# Stepperdriver.net
KiCad netlist of a schematic drawn in EAGLE
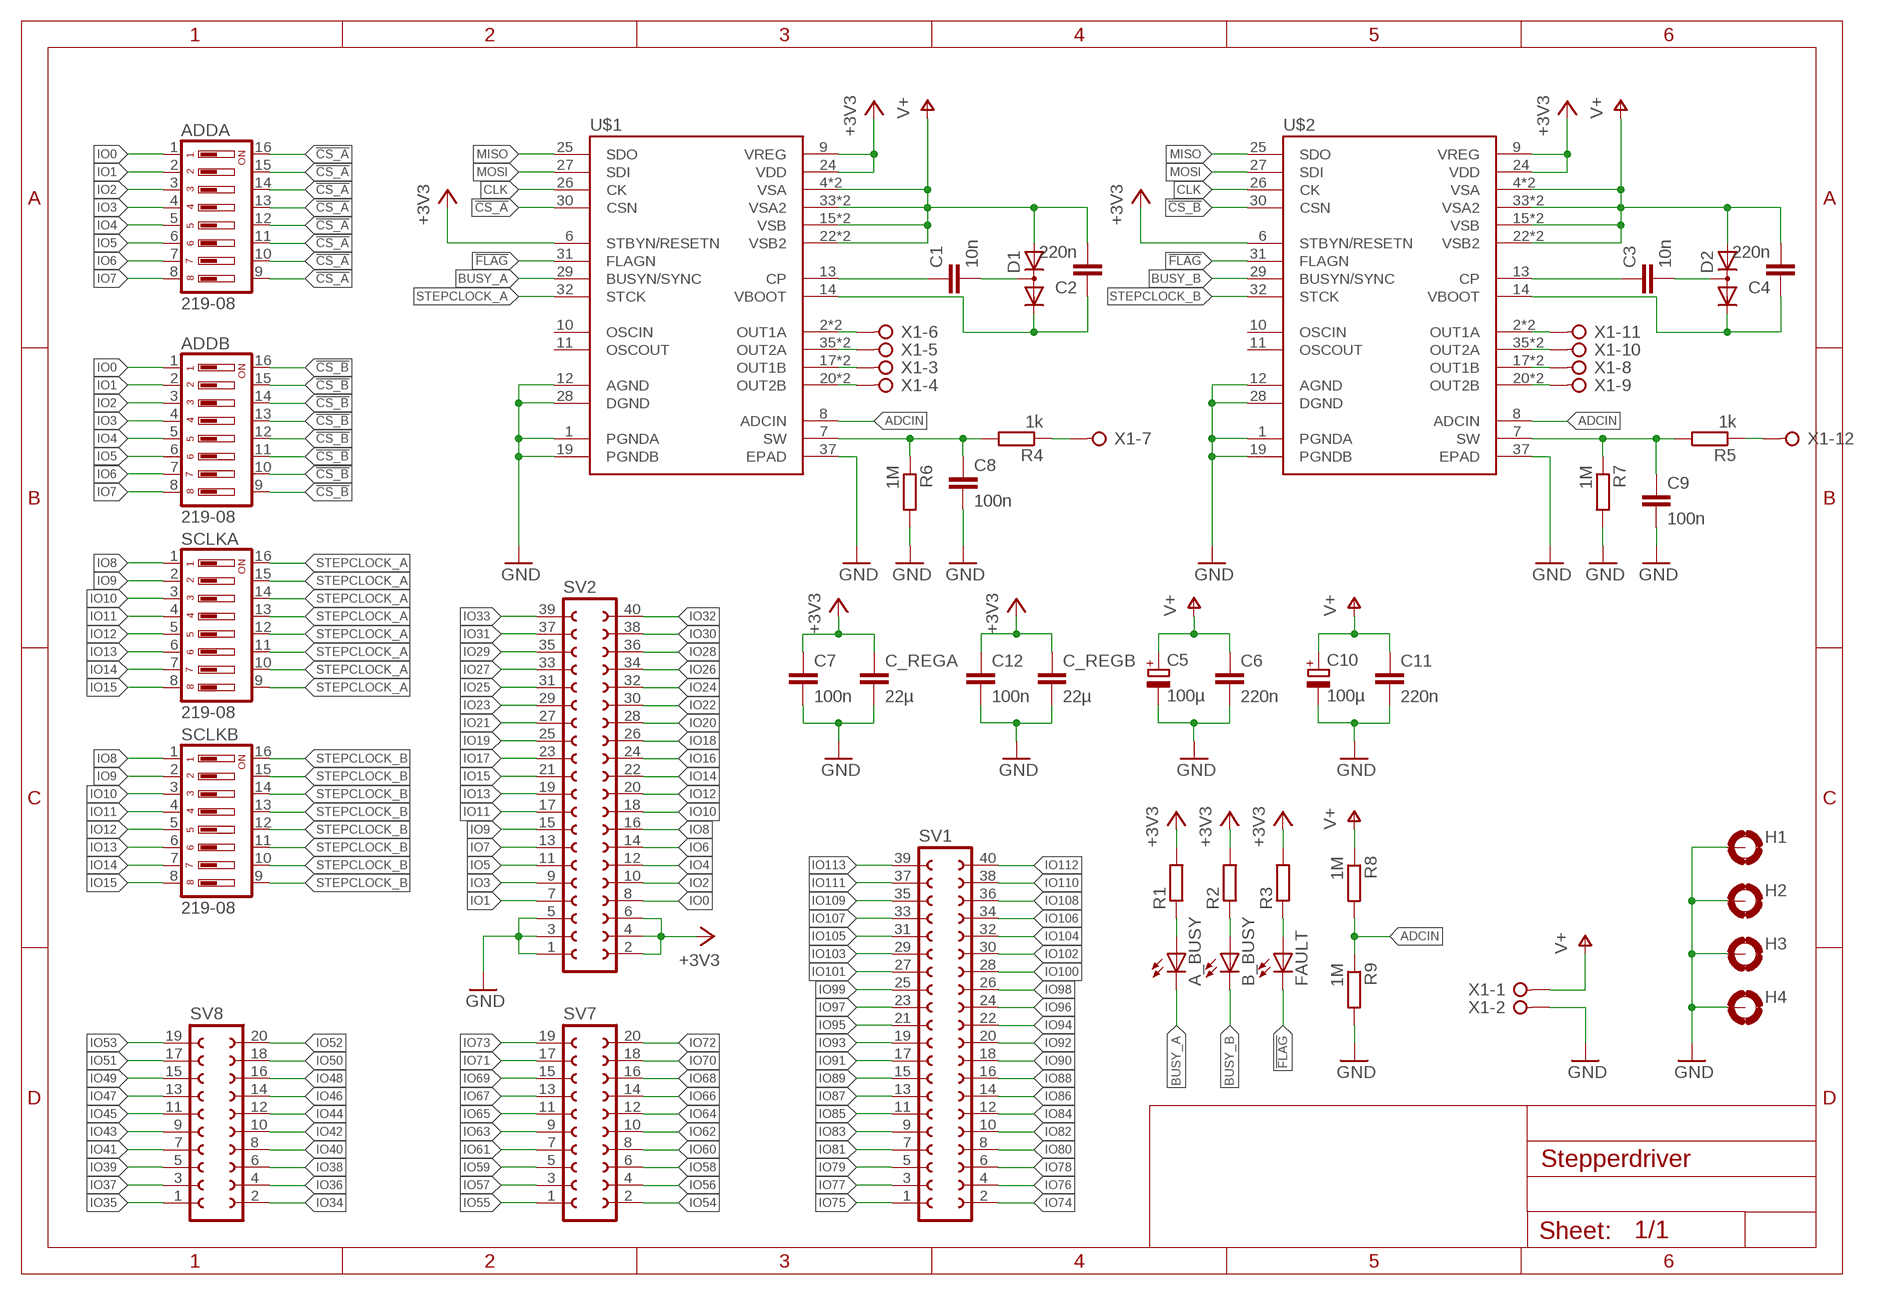
[diagram p0: schematic, sheet 1]

(export (version "E")
  (design (tool "Eeschema 10.0.6"))
  (components
    (comp (ref "ADDA")
      (value "219-08")
      (footprint "eagle-import:CTS-219-08")
      (libsource (lib "eagle-import") (part "219-08"))
    )
    (comp (ref "ADDB")
      (value "219-08")
      (footprint "eagle-import:CTS-219-08")
      (libsource (lib "eagle-import") (part "219-08"))
    )
    (comp (ref "A_BUSY")
      (value "LEDCHIP-LED0805")
      (footprint "eagle-import:CHIP-LED0805")
      (libsource (lib "eagle-import") (part "LEDCHIP-LED0805"))
    )
    (comp (ref "B_BUSY")
      (value "LEDCHIP-LED0805")
      (footprint "eagle-import:CHIP-LED0805")
      (libsource (lib "eagle-import") (part "LEDCHIP-LED0805"))
    )
    (comp (ref "C1")
      (value "10n")
      (footprint "eagle-import:C0805")
      (libsource (lib "eagle-import") (part "C-EUC0805"))
    )
    (comp (ref "C2")
      (value "220n")
      (footprint "eagle-import:C0805")
      (libsource (lib "eagle-import") (part "C-EUC0805"))
    )
    (comp (ref "C3")
      (value "10n")
      (footprint "eagle-import:C0805")
      (libsource (lib "eagle-import") (part "C-EUC0805"))
    )
    (comp (ref "C4")
      (value "220n")
      (footprint "eagle-import:C0805")
      (libsource (lib "eagle-import") (part "C-EUC0805"))
    )
    (comp (ref "C5")
      (value "100µ")
      (footprint "eagle-import:150CLZ-1010")
      (libsource (lib "eagle-import") (part "CPOL-EU150CLZ-1010"))
    )
    (comp (ref "C6")
      (value "220n")
      (footprint "eagle-import:C0805")
      (libsource (lib "eagle-import") (part "C-EUC0805"))
    )
    (comp (ref "C7")
      (value "100n")
      (footprint "eagle-import:C0805")
      (libsource (lib "eagle-import") (part "C-EUC0805"))
    )
    (comp (ref "C8")
      (value "100n")
      (footprint "eagle-import:C0805")
      (libsource (lib "eagle-import") (part "C-EUC0805"))
    )
    (comp (ref "C9")
      (value "100n")
      (footprint "eagle-import:C0805")
      (libsource (lib "eagle-import") (part "C-EUC0805"))
    )
    (comp (ref "C10")
      (value "100µ")
      (footprint "eagle-import:150CLZ-1010")
      (libsource (lib "eagle-import") (part "CPOL-EU150CLZ-1010"))
    )
    (comp (ref "C11")
      (value "220n")
      (footprint "eagle-import:C0805")
      (libsource (lib "eagle-import") (part "C-EUC0805"))
    )
    (comp (ref "C12")
      (value "100n")
      (footprint "eagle-import:C0805")
      (libsource (lib "eagle-import") (part "C-EUC0805"))
    )
    (comp (ref "C_REGA")
      (value "22µ")
      (footprint "eagle-import:C0805")
      (libsource (lib "eagle-import") (part "C-EUC0805"))
    )
    (comp (ref "C_REGB")
      (value "22µ")
      (footprint "eagle-import:C0805")
      (libsource (lib "eagle-import") (part "C-EUC0805"))
    )
    (comp (ref "D1")
      (value "DIODE_2CACA-SOT23")
      (footprint "eagle-import:SOT23")
      (libsource (lib "eagle-import") (part "DIODE_2CACA-SOT23"))
    )
    (comp (ref "D2")
      (value "DIODE_2CACA-SOT23")
      (footprint "eagle-import:SOT23")
      (libsource (lib "eagle-import") (part "DIODE_2CACA-SOT23"))
    )
    (comp (ref "FAULT")
      (value "LEDCHIP-LED0805")
      (footprint "eagle-import:CHIP-LED0805")
      (libsource (lib "eagle-import") (part "LEDCHIP-LED0805"))
    )
    (comp (ref "H1")
      (value "MOUNT-PAD-ROUND5.0")
      (footprint "eagle-import:5,0-PAD")
      (libsource (lib "eagle-import") (part "MOUNT-PAD-ROUND5.0"))
    )
    (comp (ref "H2")
      (value "MOUNT-PAD-ROUND5.0")
      (footprint "eagle-import:5,0-PAD")
      (libsource (lib "eagle-import") (part "MOUNT-PAD-ROUND5.0"))
    )
    (comp (ref "H3")
      (value "MOUNT-PAD-ROUND5.0")
      (footprint "eagle-import:5,0-PAD")
      (libsource (lib "eagle-import") (part "MOUNT-PAD-ROUND5.0"))
    )
    (comp (ref "H4")
      (value "MOUNT-PAD-ROUND5.0")
      (footprint "eagle-import:5,0-PAD")
      (libsource (lib "eagle-import") (part "MOUNT-PAD-ROUND5.0"))
    )
    (comp (ref "R1")
      (value "R-EU_R0805")
      (footprint "eagle-import:R0805")
      (libsource (lib "eagle-import") (part "R-EU_R0805"))
    )
    (comp (ref "R2")
      (value "R-EU_R0805")
      (footprint "eagle-import:R0805")
      (libsource (lib "eagle-import") (part "R-EU_R0805"))
    )
    (comp (ref "R3")
      (value "R-EU_R0805")
      (footprint "eagle-import:R0805")
      (libsource (lib "eagle-import") (part "R-EU_R0805"))
    )
    (comp (ref "R4")
      (value "1k")
      (footprint "eagle-import:R0805")
      (libsource (lib "eagle-import") (part "R-EU_R0805"))
    )
    (comp (ref "R5")
      (value "1k")
      (footprint "eagle-import:R0805")
      (libsource (lib "eagle-import") (part "R-EU_R0805"))
    )
    (comp (ref "R6")
      (value "1M")
      (footprint "eagle-import:R0805")
      (libsource (lib "eagle-import") (part "R-EU_R0805"))
    )
    (comp (ref "R7")
      (value "1M")
      (footprint "eagle-import:R0805")
      (libsource (lib "eagle-import") (part "R-EU_R0805"))
    )
    (comp (ref "R8")
      (value "1M")
      (footprint "eagle-import:R0805")
      (libsource (lib "eagle-import") (part "R-EU_R0805"))
    )
    (comp (ref "R9")
      (value "1M")
      (footprint "eagle-import:R0805")
      (libsource (lib "eagle-import") (part "R-EU_R0805"))
    )
    (comp (ref "SCLKA")
      (value "219-08")
      (footprint "eagle-import:CTS-219-08")
      (libsource (lib "eagle-import") (part "219-08"))
    )
    (comp (ref "SCLKB")
      (value "219-08")
      (footprint "eagle-import:CTS-219-08")
      (libsource (lib "eagle-import") (part "219-08"))
    )
    (comp (ref "SV1")
      (value "FE20-2")
      (footprint "eagle-import:FE20-2")
      (libsource (lib "eagle-import") (part "FE20-2"))
    )
    (comp (ref "SV2")
      (value "FE20-2")
      (footprint "eagle-import:FE20-2")
      (libsource (lib "eagle-import") (part "FE20-2"))
    )
    (comp (ref "SV7")
      (value "FE10-2")
      (footprint "eagle-import:FE10-2")
      (fields (field (name "OC_FARNELL") "unknown") (field (name "OC_NEWARK") "unknown"))
      (libsource (lib "eagle-import") (part "FE10-2"))
    )
    (comp (ref "SV8")
      (value "FE10-2")
      (footprint "eagle-import:FE10-2")
      (fields (field (name "OC_FARNELL") "unknown") (field (name "OC_NEWARK") "unknown"))
      (libsource (lib "eagle-import") (part "FE10-2"))
    )
    (comp (ref "U$1")
      (value "L6470HPOWERSO36")
      (footprint "eagle-import:SOP65P1400X360-37N")
      (libsource (lib "eagle-import") (part "L6470HPOWERSO36"))
    )
    (comp (ref "U$2")
      (value "L6470HPOWERSO36")
      (footprint "eagle-import:SOP65P1400X360-37N")
      (libsource (lib "eagle-import") (part "L6470HPOWERSO36"))
    )
    (comp (ref "X1")
      (value "W237-12P")
      (footprint "eagle-import:W237-12P")
      (libsource (lib "eagle-import") (part "W237-12P"))
    )
  )
  (nets
    (net (code "1") (name "+3V3") (class "Default")
      (node (ref "C12") (pin "1") (pinfunction "1_1") (pintype "passive"))
      (node (ref "C7") (pin "1") (pinfunction "1_1") (pintype "passive"))
      (node (ref "C_REGA") (pin "1") (pinfunction "1_1") (pintype "passive"))
      (node (ref "C_REGB") (pin "1") (pinfunction "1_1") (pintype "passive"))
      (node (ref "R1") (pin "2") (pinfunction "2_2") (pintype "passive"))
      (node (ref "R2") (pin "2") (pinfunction "2_2") (pintype "passive"))
      (node (ref "R3") (pin "2") (pinfunction "2_2") (pintype "passive"))
      (node (ref "SV2") (pin "2") (pinfunction "2_2") (pintype "passive"))
      (node (ref "SV2") (pin "4") (pinfunction "4_4") (pintype "passive"))
      (node (ref "SV2") (pin "6") (pinfunction "6_6") (pintype "passive"))
      (node (ref "U$1") (pin "24") (pinfunction "VDD_24") (pintype "bidirectional"))
      (node (ref "U$1") (pin "6") (pinfunction "STBYN/RESETN_6") (pintype "bidirectional"))
      (node (ref "U$1") (pin "9") (pinfunction "VREG_9") (pintype "bidirectional"))
      (node (ref "U$2") (pin "24") (pinfunction "VDD_24") (pintype "bidirectional"))
      (node (ref "U$2") (pin "6") (pinfunction "STBYN/RESETN_6") (pintype "bidirectional"))
      (node (ref "U$2") (pin "9") (pinfunction "VREG_9") (pintype "bidirectional"))
    )
    (net (code "2") (name "/~{CS_A}") (class "Default")
      (node (ref "ADDA") (pin "10") (pinfunction "10_10") (pintype "passive"))
      (node (ref "ADDA") (pin "11") (pinfunction "11_11") (pintype "passive"))
      (node (ref "ADDA") (pin "12") (pinfunction "12_12") (pintype "passive"))
      (node (ref "ADDA") (pin "13") (pinfunction "13_13") (pintype "passive"))
      (node (ref "ADDA") (pin "14") (pinfunction "14_14") (pintype "passive"))
      (node (ref "ADDA") (pin "15") (pinfunction "15_15") (pintype "passive"))
      (node (ref "ADDA") (pin "16") (pinfunction "16_16") (pintype "passive"))
      (node (ref "ADDA") (pin "9") (pinfunction "9_9") (pintype "passive"))
      (node (ref "U$1") (pin "30") (pinfunction "CSN_30") (pintype "bidirectional"))
    )
    (net (code "3") (name "/~{CS_B}") (class "Default")
      (node (ref "ADDB") (pin "10") (pinfunction "10_10") (pintype "passive"))
      (node (ref "ADDB") (pin "11") (pinfunction "11_11") (pintype "passive"))
      (node (ref "ADDB") (pin "12") (pinfunction "12_12") (pintype "passive"))
      (node (ref "ADDB") (pin "13") (pinfunction "13_13") (pintype "passive"))
      (node (ref "ADDB") (pin "14") (pinfunction "14_14") (pintype "passive"))
      (node (ref "ADDB") (pin "15") (pinfunction "15_15") (pintype "passive"))
      (node (ref "ADDB") (pin "16") (pinfunction "16_16") (pintype "passive"))
      (node (ref "ADDB") (pin "9") (pinfunction "9_9") (pintype "passive"))
      (node (ref "U$2") (pin "30") (pinfunction "CSN_30") (pintype "bidirectional"))
    )
    (net (code "4") (name "/~{FLAG}") (class "Default")
      (node (ref "FAULT") (pin "C") (pinfunction "C_C") (pintype "passive"))
      (node (ref "U$1") (pin "31") (pinfunction "FLAGN_31") (pintype "bidirectional"))
      (node (ref "U$2") (pin "31") (pinfunction "FLAGN_31") (pintype "bidirectional"))
    )
    (net (code "5") (name "ADCIN") (class "Default")
      (node (ref "R8") (pin "2") (pinfunction "2_2") (pintype "passive"))
      (node (ref "R9") (pin "1") (pinfunction "1_1") (pintype "passive"))
      (node (ref "U$1") (pin "8") (pinfunction "ADCIN_8") (pintype "bidirectional"))
      (node (ref "U$2") (pin "8") (pinfunction "ADCIN_8") (pintype "bidirectional"))
    )
    (net (code "6") (name "BUSY_A") (class "Default")
      (node (ref "A_BUSY") (pin "C") (pinfunction "C_C") (pintype "passive"))
      (node (ref "U$1") (pin "29") (pinfunction "BUSYN/SYNC_29") (pintype "bidirectional"))
    )
    (net (code "7") (name "BUSY_B") (class "Default")
      (node (ref "B_BUSY") (pin "C") (pinfunction "C_C") (pintype "passive"))
      (node (ref "U$2") (pin "29") (pinfunction "BUSYN/SYNC_29") (pintype "bidirectional"))
    )
    (net (code "8") (name "CLK") (class "Default")
      (node (ref "U$1") (pin "26") (pinfunction "CK_26") (pintype "bidirectional"))
      (node (ref "U$2") (pin "26") (pinfunction "CK_26") (pintype "bidirectional"))
    )
    (net (code "9") (name "GND") (class "Default")
      (node (ref "C10") (pin "-") (pinfunction "-_-") (pintype "passive"))
      (node (ref "C11") (pin "2") (pinfunction "2_2") (pintype "passive"))
      (node (ref "C12") (pin "2") (pinfunction "2_2") (pintype "passive"))
      (node (ref "C5") (pin "-") (pinfunction "-_-") (pintype "passive"))
      (node (ref "C6") (pin "2") (pinfunction "2_2") (pintype "passive"))
      (node (ref "C7") (pin "2") (pinfunction "2_2") (pintype "passive"))
      (node (ref "C8") (pin "2") (pinfunction "2_2") (pintype "passive"))
      (node (ref "C9") (pin "2") (pinfunction "2_2") (pintype "passive"))
      (node (ref "C_REGA") (pin "2") (pinfunction "2_2") (pintype "passive"))
      (node (ref "C_REGB") (pin "2") (pinfunction "2_2") (pintype "passive"))
      (node (ref "H1") (pin "B5") (pinfunction "MOUNT_B5") (pintype "passive"))
      (node (ref "H2") (pin "B5") (pinfunction "MOUNT_B5") (pintype "passive"))
      (node (ref "H3") (pin "B5") (pinfunction "MOUNT_B5") (pintype "passive"))
      (node (ref "H4") (pin "B5") (pinfunction "MOUNT_B5") (pintype "passive"))
      (node (ref "R6") (pin "2") (pinfunction "2_2") (pintype "passive"))
      (node (ref "R7") (pin "2") (pinfunction "2_2") (pintype "passive"))
      (node (ref "R9") (pin "2") (pinfunction "2_2") (pintype "passive"))
      (node (ref "SV2") (pin "1") (pinfunction "1_1") (pintype "passive"))
      (node (ref "SV2") (pin "3") (pinfunction "3_3") (pintype "passive"))
      (node (ref "SV2") (pin "5") (pinfunction "5_5") (pintype "passive"))
      (node (ref "U$1") (pin "1") (pinfunction "PGNDA_1") (pintype "bidirectional"))
      (node (ref "U$1") (pin "12") (pinfunction "AGND_12") (pintype "bidirectional"))
      (node (ref "U$1") (pin "19") (pinfunction "PGNDB_19") (pintype "bidirectional"))
      (node (ref "U$1") (pin "28") (pinfunction "DGND_28") (pintype "bidirectional"))
      (node (ref "U$1") (pin "37") (pinfunction "EPAD_37") (pintype "bidirectional"))
      (node (ref "U$2") (pin "1") (pinfunction "PGNDA_1") (pintype "bidirectional"))
      (node (ref "U$2") (pin "12") (pinfunction "AGND_12") (pintype "bidirectional"))
      (node (ref "U$2") (pin "19") (pinfunction "PGNDB_19") (pintype "bidirectional"))
      (node (ref "U$2") (pin "28") (pinfunction "DGND_28") (pintype "bidirectional"))
      (node (ref "U$2") (pin "37") (pinfunction "EPAD_37") (pintype "bidirectional"))
      (node (ref "X1") (pin "2") (pinfunction "KL_2") (pintype "passive"))
    )
    (net (code "10") (name "IO0") (class "Default")
      (node (ref "ADDA") (pin "1") (pinfunction "1_1") (pintype "passive"))
      (node (ref "ADDB") (pin "1") (pinfunction "1_1") (pintype "passive"))
      (node (ref "SV2") (pin "8") (pinfunction "8_8") (pintype "passive"))
    )
    (net (code "11") (name "IO1") (class "Default")
      (node (ref "ADDA") (pin "2") (pinfunction "2_2") (pintype "passive"))
      (node (ref "ADDB") (pin "2") (pinfunction "2_2") (pintype "passive"))
      (node (ref "SV2") (pin "7") (pinfunction "7_7") (pintype "passive"))
    )
    (net (code "12") (name "IO2") (class "Default")
      (node (ref "ADDA") (pin "3") (pinfunction "3_3") (pintype "passive"))
      (node (ref "ADDB") (pin "3") (pinfunction "3_3") (pintype "passive"))
      (node (ref "SV2") (pin "10") (pinfunction "10_10") (pintype "passive"))
    )
    (net (code "13") (name "IO3") (class "Default")
      (node (ref "ADDA") (pin "4") (pinfunction "4_4") (pintype "passive"))
      (node (ref "ADDB") (pin "4") (pinfunction "4_4") (pintype "passive"))
      (node (ref "SV2") (pin "9") (pinfunction "9_9") (pintype "passive"))
    )
    (net (code "14") (name "IO4") (class "Default")
      (node (ref "ADDA") (pin "5") (pinfunction "5_5") (pintype "passive"))
      (node (ref "ADDB") (pin "5") (pinfunction "5_5") (pintype "passive"))
      (node (ref "SV2") (pin "12") (pinfunction "12_12") (pintype "passive"))
    )
    (net (code "15") (name "IO5") (class "Default")
      (node (ref "ADDA") (pin "6") (pinfunction "6_6") (pintype "passive"))
      (node (ref "ADDB") (pin "6") (pinfunction "6_6") (pintype "passive"))
      (node (ref "SV2") (pin "11") (pinfunction "11_11") (pintype "passive"))
    )
    (net (code "16") (name "IO6") (class "Default")
      (node (ref "ADDA") (pin "7") (pinfunction "7_7") (pintype "passive"))
      (node (ref "ADDB") (pin "7") (pinfunction "7_7") (pintype "passive"))
      (node (ref "SV2") (pin "14") (pinfunction "14_14") (pintype "passive"))
    )
    (net (code "17") (name "IO7") (class "Default")
      (node (ref "ADDA") (pin "8") (pinfunction "8_8") (pintype "passive"))
      (node (ref "ADDB") (pin "8") (pinfunction "8_8") (pintype "passive"))
      (node (ref "SV2") (pin "13") (pinfunction "13_13") (pintype "passive"))
    )
    (net (code "18") (name "IO8") (class "Default")
      (node (ref "SCLKA") (pin "1") (pinfunction "1_1") (pintype "passive"))
      (node (ref "SCLKB") (pin "1") (pinfunction "1_1") (pintype "passive"))
      (node (ref "SV2") (pin "16") (pinfunction "16_16") (pintype "passive"))
    )
    (net (code "19") (name "IO9") (class "Default")
      (node (ref "SCLKA") (pin "2") (pinfunction "2_2") (pintype "passive"))
      (node (ref "SCLKB") (pin "2") (pinfunction "2_2") (pintype "passive"))
      (node (ref "SV2") (pin "15") (pinfunction "15_15") (pintype "passive"))
    )
    (net (code "20") (name "IO10") (class "Default")
      (node (ref "SCLKA") (pin "3") (pinfunction "3_3") (pintype "passive"))
      (node (ref "SCLKB") (pin "3") (pinfunction "3_3") (pintype "passive"))
      (node (ref "SV2") (pin "18") (pinfunction "18_18") (pintype "passive"))
    )
    (net (code "21") (name "IO11") (class "Default")
      (node (ref "SCLKA") (pin "4") (pinfunction "4_4") (pintype "passive"))
      (node (ref "SCLKB") (pin "4") (pinfunction "4_4") (pintype "passive"))
      (node (ref "SV2") (pin "17") (pinfunction "17_17") (pintype "passive"))
    )
    (net (code "22") (name "IO12") (class "Default")
      (node (ref "SCLKA") (pin "5") (pinfunction "5_5") (pintype "passive"))
      (node (ref "SCLKB") (pin "5") (pinfunction "5_5") (pintype "passive"))
      (node (ref "SV2") (pin "20") (pinfunction "20_20") (pintype "passive"))
    )
    (net (code "23") (name "IO13") (class "Default")
      (node (ref "SCLKA") (pin "6") (pinfunction "6_6") (pintype "passive"))
      (node (ref "SCLKB") (pin "6") (pinfunction "6_6") (pintype "passive"))
      (node (ref "SV2") (pin "19") (pinfunction "19_19") (pintype "passive"))
    )
    (net (code "24") (name "IO14") (class "Default")
      (node (ref "SCLKA") (pin "7") (pinfunction "7_7") (pintype "passive"))
      (node (ref "SCLKB") (pin "7") (pinfunction "7_7") (pintype "passive"))
      (node (ref "SV2") (pin "22") (pinfunction "22_22") (pintype "passive"))
    )
    (net (code "25") (name "IO15") (class "Default")
      (node (ref "SCLKA") (pin "8") (pinfunction "8_8") (pintype "passive"))
      (node (ref "SCLKB") (pin "8") (pinfunction "8_8") (pintype "passive"))
      (node (ref "SV2") (pin "21") (pinfunction "21_21") (pintype "passive"))
    )
    (net (code "26") (name "IO16") (class "Default")
      (node (ref "SV2") (pin "24") (pinfunction "24_24") (pintype "passive"))
    )
    (net (code "27") (name "IO17") (class "Default")
      (node (ref "SV2") (pin "23") (pinfunction "23_23") (pintype "passive"))
    )
    (net (code "28") (name "IO18") (class "Default")
      (node (ref "SV2") (pin "26") (pinfunction "26_26") (pintype "passive"))
    )
    (net (code "29") (name "IO19") (class "Default")
      (node (ref "SV2") (pin "25") (pinfunction "25_25") (pintype "passive"))
    )
    (net (code "30") (name "IO20") (class "Default")
      (node (ref "SV2") (pin "28") (pinfunction "28_28") (pintype "passive"))
    )
    (net (code "31") (name "IO21") (class "Default")
      (node (ref "SV2") (pin "27") (pinfunction "27_27") (pintype "passive"))
    )
    (net (code "32") (name "IO22") (class "Default")
      (node (ref "SV2") (pin "30") (pinfunction "30_30") (pintype "passive"))
    )
    (net (code "33") (name "IO23") (class "Default")
      (node (ref "SV2") (pin "29") (pinfunction "29_29") (pintype "passive"))
    )
    (net (code "34") (name "IO24") (class "Default")
      (node (ref "SV2") (pin "32") (pinfunction "32_32") (pintype "passive"))
    )
    (net (code "35") (name "IO25") (class "Default")
      (node (ref "SV2") (pin "31") (pinfunction "31_31") (pintype "passive"))
    )
    (net (code "36") (name "IO26") (class "Default")
      (node (ref "SV2") (pin "34") (pinfunction "34_34") (pintype "passive"))
    )
    (net (code "37") (name "IO27") (class "Default")
      (node (ref "SV2") (pin "33") (pinfunction "33_33") (pintype "passive"))
    )
    (net (code "38") (name "IO28") (class "Default")
      (node (ref "SV2") (pin "36") (pinfunction "36_36") (pintype "passive"))
    )
    (net (code "39") (name "IO29") (class "Default")
      (node (ref "SV2") (pin "35") (pinfunction "35_35") (pintype "passive"))
    )
    (net (code "40") (name "IO30") (class "Default")
      (node (ref "SV2") (pin "38") (pinfunction "38_38") (pintype "passive"))
    )
    (net (code "41") (name "IO31") (class "Default")
      (node (ref "SV2") (pin "37") (pinfunction "37_37") (pintype "passive"))
    )
    (net (code "42") (name "IO32") (class "Default")
      (node (ref "SV2") (pin "40") (pinfunction "40_40") (pintype "passive"))
    )
    (net (code "43") (name "IO33") (class "Default")
      (node (ref "SV2") (pin "39") (pinfunction "39_39") (pintype "passive"))
    )
    (net (code "44") (name "IO34") (class "Default")
      (node (ref "SV8") (pin "2") (pinfunction "2_2") (pintype "passive"))
    )
    (net (code "45") (name "IO35") (class "Default")
      (node (ref "SV8") (pin "1") (pinfunction "1_1") (pintype "passive"))
    )
    (net (code "46") (name "IO36") (class "Default")
      (node (ref "SV8") (pin "4") (pinfunction "4_4") (pintype "passive"))
    )
    (net (code "47") (name "IO37") (class "Default")
      (node (ref "SV8") (pin "3") (pinfunction "3_3") (pintype "passive"))
    )
    (net (code "48") (name "IO38") (class "Default")
      (node (ref "SV8") (pin "6") (pinfunction "6_6") (pintype "passive"))
    )
    (net (code "49") (name "IO39") (class "Default")
      (node (ref "SV8") (pin "5") (pinfunction "5_5") (pintype "passive"))
    )
    (net (code "50") (name "IO40") (class "Default")
      (node (ref "SV8") (pin "8") (pinfunction "8_8") (pintype "passive"))
    )
    (net (code "51") (name "IO41") (class "Default")
      (node (ref "SV8") (pin "7") (pinfunction "7_7") (pintype "passive"))
    )
    (net (code "52") (name "IO42") (class "Default")
      (node (ref "SV8") (pin "10") (pinfunction "10_10") (pintype "passive"))
    )
    (net (code "53") (name "IO43") (class "Default")
      (node (ref "SV8") (pin "9") (pinfunction "9_9") (pintype "passive"))
    )
    (net (code "54") (name "IO44") (class "Default")
      (node (ref "SV8") (pin "12") (pinfunction "12_12") (pintype "passive"))
    )
    (net (code "55") (name "IO45") (class "Default")
      (node (ref "SV8") (pin "11") (pinfunction "11_11") (pintype "passive"))
    )
    (net (code "56") (name "IO46") (class "Default")
      (node (ref "SV8") (pin "14") (pinfunction "14_14") (pintype "passive"))
    )
    (net (code "57") (name "IO47") (class "Default")
      (node (ref "SV8") (pin "13") (pinfunction "13_13") (pintype "passive"))
    )
    (net (code "58") (name "IO48") (class "Default")
      (node (ref "SV8") (pin "16") (pinfunction "16_16") (pintype "passive"))
    )
    (net (code "59") (name "IO49") (class "Default")
      (node (ref "SV8") (pin "15") (pinfunction "15_15") (pintype "passive"))
    )
    (net (code "60") (name "IO50") (class "Default")
      (node (ref "SV8") (pin "18") (pinfunction "18_18") (pintype "passive"))
    )
    (net (code "61") (name "IO51") (class "Default")
      (node (ref "SV8") (pin "17") (pinfunction "17_17") (pintype "passive"))
    )
    (net (code "62") (name "IO52") (class "Default")
      (node (ref "SV8") (pin "20") (pinfunction "20_20") (pintype "passive"))
    )
    (net (code "63") (name "IO53") (class "Default")
      (node (ref "SV8") (pin "19") (pinfunction "19_19") (pintype "passive"))
    )
    (net (code "64") (name "IO54") (class "Default")
      (node (ref "SV7") (pin "2") (pinfunction "2_2") (pintype "passive"))
    )
    (net (code "65") (name "IO55") (class "Default")
      (node (ref "SV7") (pin "1") (pinfunction "1_1") (pintype "passive"))
    )
    (net (code "66") (name "IO56") (class "Default")
      (node (ref "SV7") (pin "4") (pinfunction "4_4") (pintype "passive"))
    )
    (net (code "67") (name "IO57") (class "Default")
      (node (ref "SV7") (pin "3") (pinfunction "3_3") (pintype "passive"))
    )
    (net (code "68") (name "IO58") (class "Default")
      (node (ref "SV7") (pin "6") (pinfunction "6_6") (pintype "passive"))
    )
    (net (code "69") (name "IO59") (class "Default")
      (node (ref "SV7") (pin "5") (pinfunction "5_5") (pintype "passive"))
    )
    (net (code "70") (name "IO60") (class "Default")
      (node (ref "SV7") (pin "8") (pinfunction "8_8") (pintype "passive"))
    )
    (net (code "71") (name "IO61") (class "Default")
      (node (ref "SV7") (pin "7") (pinfunction "7_7") (pintype "passive"))
    )
    (net (code "72") (name "IO62") (class "Default")
      (node (ref "SV7") (pin "10") (pinfunction "10_10") (pintype "passive"))
    )
    (net (code "73") (name "IO63") (class "Default")
      (node (ref "SV7") (pin "9") (pinfunction "9_9") (pintype "passive"))
    )
    (net (code "74") (name "IO64") (class "Default")
      (node (ref "SV7") (pin "12") (pinfunction "12_12") (pintype "passive"))
    )
    (net (code "75") (name "IO65") (class "Default")
      (node (ref "SV7") (pin "11") (pinfunction "11_11") (pintype "passive"))
    )
    (net (code "76") (name "IO66") (class "Default")
      (node (ref "SV7") (pin "14") (pinfunction "14_14") (pintype "passive"))
    )
    (net (code "77") (name "IO67") (class "Default")
      (node (ref "SV7") (pin "13") (pinfunction "13_13") (pintype "passive"))
    )
    (net (code "78") (name "IO68") (class "Default")
      (node (ref "SV7") (pin "16") (pinfunction "16_16") (pintype "passive"))
    )
    (net (code "79") (name "IO69") (class "Default")
      (node (ref "SV7") (pin "15") (pinfunction "15_15") (pintype "passive"))
    )
    (net (code "80") (name "IO70") (class "Default")
      (node (ref "SV7") (pin "18") (pinfunction "18_18") (pintype "passive"))
    )
    (net (code "81") (name "IO71") (class "Default")
      (node (ref "SV7") (pin "17") (pinfunction "17_17") (pintype "passive"))
    )
    (net (code "82") (name "IO72") (class "Default")
      (node (ref "SV7") (pin "20") (pinfunction "20_20") (pintype "passive"))
    )
    (net (code "83") (name "IO73") (class "Default")
      (node (ref "SV7") (pin "19") (pinfunction "19_19") (pintype "passive"))
    )
    (net (code "84") (name "IO74") (class "Default")
      (node (ref "SV1") (pin "2") (pinfunction "2_2") (pintype "passive"))
    )
    (net (code "85") (name "IO75") (class "Default")
      (node (ref "SV1") (pin "1") (pinfunction "1_1") (pintype "passive"))
    )
    (net (code "86") (name "IO76") (class "Default")
      (node (ref "SV1") (pin "4") (pinfunction "4_4") (pintype "passive"))
    )
    (net (code "87") (name "IO77") (class "Default")
      (node (ref "SV1") (pin "3") (pinfunction "3_3") (pintype "passive"))
    )
    (net (code "88") (name "IO78") (class "Default")
      (node (ref "SV1") (pin "6") (pinfunction "6_6") (pintype "passive"))
    )
    (net (code "89") (name "IO79") (class "Default")
      (node (ref "SV1") (pin "5") (pinfunction "5_5") (pintype "passive"))
    )
    (net (code "90") (name "IO80") (class "Default")
      (node (ref "SV1") (pin "8") (pinfunction "8_8") (pintype "passive"))
    )
    (net (code "91") (name "IO81") (class "Default")
      (node (ref "SV1") (pin "7") (pinfunction "7_7") (pintype "passive"))
    )
    (net (code "92") (name "IO82") (class "Default")
      (node (ref "SV1") (pin "10") (pinfunction "10_10") (pintype "passive"))
    )
    (net (code "93") (name "IO83") (class "Default")
      (node (ref "SV1") (pin "9") (pinfunction "9_9") (pintype "passive"))
    )
    (net (code "94") (name "IO84") (class "Default")
      (node (ref "SV1") (pin "12") (pinfunction "12_12") (pintype "passive"))
    )
    (net (code "95") (name "IO85") (class "Default")
      (node (ref "SV1") (pin "11") (pinfunction "11_11") (pintype "passive"))
    )
    (net (code "96") (name "IO86") (class "Default")
      (node (ref "SV1") (pin "14") (pinfunction "14_14") (pintype "passive"))
    )
    (net (code "97") (name "IO87") (class "Default")
      (node (ref "SV1") (pin "13") (pinfunction "13_13") (pintype "passive"))
    )
    (net (code "98") (name "IO88") (class "Default")
      (node (ref "SV1") (pin "16") (pinfunction "16_16") (pintype "passive"))
    )
    (net (code "99") (name "IO89") (class "Default")
      (node (ref "SV1") (pin "15") (pinfunction "15_15") (pintype "passive"))
    )
    (net (code "100") (name "IO90") (class "Default")
      (node (ref "SV1") (pin "18") (pinfunction "18_18") (pintype "passive"))
    )
    (net (code "101") (name "IO91") (class "Default")
      (node (ref "SV1") (pin "17") (pinfunction "17_17") (pintype "passive"))
    )
    (net (code "102") (name "IO92") (class "Default")
      (node (ref "SV1") (pin "20") (pinfunction "20_20") (pintype "passive"))
    )
    (net (code "103") (name "IO93") (class "Default")
      (node (ref "SV1") (pin "19") (pinfunction "19_19") (pintype "passive"))
    )
    (net (code "104") (name "IO94") (class "Default")
      (node (ref "SV1") (pin "22") (pinfunction "22_22") (pintype "passive"))
    )
    (net (code "105") (name "IO95") (class "Default")
      (node (ref "SV1") (pin "21") (pinfunction "21_21") (pintype "passive"))
    )
    (net (code "106") (name "IO96") (class "Default")
      (node (ref "SV1") (pin "24") (pinfunction "24_24") (pintype "passive"))
    )
    (net (code "107") (name "IO97") (class "Default")
      (node (ref "SV1") (pin "23") (pinfunction "23_23") (pintype "passive"))
    )
    (net (code "108") (name "IO98") (class "Default")
      (node (ref "SV1") (pin "26") (pinfunction "26_26") (pintype "passive"))
    )
    (net (code "109") (name "IO99") (class "Default")
      (node (ref "SV1") (pin "25") (pinfunction "25_25") (pintype "passive"))
    )
    (net (code "110") (name "IO100") (class "Default")
      (node (ref "SV1") (pin "28") (pinfunction "28_28") (pintype "passive"))
    )
    (net (code "111") (name "IO101") (class "Default")
      (node (ref "SV1") (pin "27") (pinfunction "27_27") (pintype "passive"))
    )
    (net (code "112") (name "IO102") (class "Default")
      (node (ref "SV1") (pin "30") (pinfunction "30_30") (pintype "passive"))
    )
    (net (code "113") (name "IO103") (class "Default")
      (node (ref "SV1") (pin "29") (pinfunction "29_29") (pintype "passive"))
    )
    (net (code "114") (name "IO104") (class "Default")
      (node (ref "SV1") (pin "32") (pinfunction "32_32") (pintype "passive"))
    )
    (net (code "115") (name "IO105") (class "Default")
      (node (ref "SV1") (pin "31") (pinfunction "31_31") (pintype "passive"))
    )
    (net (code "116") (name "IO106") (class "Default")
      (node (ref "SV1") (pin "34") (pinfunction "34_34") (pintype "passive"))
    )
    (net (code "117") (name "IO107") (class "Default")
      (node (ref "SV1") (pin "33") (pinfunction "33_33") (pintype "passive"))
    )
    (net (code "118") (name "IO108") (class "Default")
      (node (ref "SV1") (pin "36") (pinfunction "36_36") (pintype "passive"))
    )
    (net (code "119") (name "IO109") (class "Default")
      (node (ref "SV1") (pin "35") (pinfunction "35_35") (pintype "passive"))
    )
    (net (code "120") (name "IO110") (class "Default")
      (node (ref "SV1") (pin "38") (pinfunction "38_38") (pintype "passive"))
    )
    (net (code "121") (name "IO111") (class "Default")
      (node (ref "SV1") (pin "37") (pinfunction "37_37") (pintype "passive"))
    )
    (net (code "122") (name "IO112") (class "Default")
      (node (ref "SV1") (pin "40") (pinfunction "40_40") (pintype "passive"))
    )
    (net (code "123") (name "IO113") (class "Default")
      (node (ref "SV1") (pin "39") (pinfunction "39_39") (pintype "passive"))
    )
    (net (code "124") (name "MISO") (class "Default")
      (node (ref "U$1") (pin "25") (pinfunction "SDO_25") (pintype "bidirectional"))
      (node (ref "U$2") (pin "25") (pinfunction "SDO_25") (pintype "bidirectional"))
    )
    (net (code "125") (name "MOSI") (class "Default")
      (node (ref "U$1") (pin "27") (pinfunction "SDI_27") (pintype "bidirectional"))
      (node (ref "U$2") (pin "27") (pinfunction "SDI_27") (pintype "bidirectional"))
    )
    (net (code "126") (name "Net-(A_BUSY-PadA)") (class "Default")
      (node (ref "A_BUSY") (pin "A") (pinfunction "A_A") (pintype "passive"))
      (node (ref "R1") (pin "1") (pinfunction "1_1") (pintype "passive"))
    )
    (net (code "127") (name "Net-(B_BUSY-PadA)") (class "Default")
      (node (ref "B_BUSY") (pin "A") (pinfunction "A_A") (pintype "passive"))
      (node (ref "R2") (pin "1") (pinfunction "1_1") (pintype "passive"))
    )
    (net (code "128") (name "Net-(D1-AC)") (class "Default")
      (node (ref "C1") (pin "2") (pinfunction "2_2") (pintype "passive"))
      (node (ref "D1") (pin "3") (pinfunction "AC_3") (pintype "passive"))
    )
    (net (code "129") (name "Net-(D1-C)") (class "Default")
      (node (ref "C2") (pin "1") (pinfunction "1_1") (pintype "passive"))
      (node (ref "D1") (pin "2") (pinfunction "C_2") (pintype "passive"))
      (node (ref "U$1") (pin "14") (pinfunction "VBOOT_14") (pintype "bidirectional"))
    )
    (net (code "130") (name "Net-(D2-AC)") (class "Default")
      (node (ref "C3") (pin "2") (pinfunction "2_2") (pintype "passive"))
      (node (ref "D2") (pin "3") (pinfunction "AC_3") (pintype "passive"))
    )
    (net (code "131") (name "Net-(D2-C)") (class "Default")
      (node (ref "C4") (pin "1") (pinfunction "1_1") (pintype "passive"))
      (node (ref "D2") (pin "2") (pinfunction "C_2") (pintype "passive"))
      (node (ref "U$2") (pin "14") (pinfunction "VBOOT_14") (pintype "bidirectional"))
    )
    (net (code "132") (name "Net-(FAULT-PadA)") (class "Default")
      (node (ref "FAULT") (pin "A") (pinfunction "A_A") (pintype "passive"))
      (node (ref "R3") (pin "1") (pinfunction "1_1") (pintype "passive"))
    )
    (net (code "133") (name "Net-(U$1-CP)") (class "Default")
      (node (ref "C1") (pin "1") (pinfunction "1_1") (pintype "passive"))
      (node (ref "U$1") (pin "13") (pinfunction "CP_13") (pintype "bidirectional"))
    )
    (net (code "134") (name "Net-(U$1-SW)") (class "Default")
      (node (ref "C8") (pin "1") (pinfunction "1_1") (pintype "passive"))
      (node (ref "R4") (pin "2") (pinfunction "2_2") (pintype "passive"))
      (node (ref "R6") (pin "1") (pinfunction "1_1") (pintype "passive"))
      (node (ref "U$1") (pin "7") (pinfunction "SW_7") (pintype "bidirectional"))
    )
    (net (code "135") (name "Net-(U$2-CP)") (class "Default")
      (node (ref "C3") (pin "1") (pinfunction "1_1") (pintype "passive"))
      (node (ref "U$2") (pin "13") (pinfunction "CP_13") (pintype "bidirectional"))
    )
    (net (code "136") (name "Net-(U$2-SW)") (class "Default")
      (node (ref "C9") (pin "1") (pinfunction "1_1") (pintype "passive"))
      (node (ref "R5") (pin "2") (pinfunction "2_2") (pintype "passive"))
      (node (ref "R7") (pin "1") (pinfunction "1_1") (pintype "passive"))
      (node (ref "U$2") (pin "7") (pinfunction "SW_7") (pintype "bidirectional"))
    )
    (net (code "137") (name "Net-(X1B-KL)") (class "Default")
      (node (ref "U$2") (pin "35") (pinfunction "OUT2A_35") (pintype "bidirectional"))
      (node (ref "U$2") (pin "36") (pinfunction "OUT2A_36") (pintype "bidirectional"))
      (node (ref "X1") (pin "10") (pinfunction "KL_10") (pintype "passive"))
    )
    (net (code "138") (name "Net-(X1C-KL)") (class "Default")
      (node (ref "U$2") (pin "2") (pinfunction "OUT1A_2") (pintype "bidirectional"))
      (node (ref "U$2") (pin "3") (pinfunction "OUT1A_3") (pintype "bidirectional"))
      (node (ref "X1") (pin "11") (pinfunction "KL_11") (pintype "passive"))
    )
    (net (code "139") (name "Net-(X1D-KL)") (class "Default")
      (node (ref "R5") (pin "1") (pinfunction "1_1") (pintype "passive"))
      (node (ref "X1") (pin "12") (pinfunction "KL_12") (pintype "passive"))
    )
    (net (code "140") (name "Net-(X1F-KL)") (class "Default")
      (node (ref "U$1") (pin "17") (pinfunction "OUT1B_17") (pintype "bidirectional"))
      (node (ref "U$1") (pin "18") (pinfunction "OUT1B_18") (pintype "bidirectional"))
      (node (ref "X1") (pin "3") (pinfunction "KL_3") (pintype "passive"))
    )
    (net (code "141") (name "Net-(X1G-KL)") (class "Default")
      (node (ref "U$1") (pin "20") (pinfunction "OUT2B_20") (pintype "bidirectional"))
      (node (ref "U$1") (pin "21") (pinfunction "OUT2B_21") (pintype "bidirectional"))
      (node (ref "X1") (pin "4") (pinfunction "KL_4") (pintype "passive"))
    )
    (net (code "142") (name "Net-(X1H-KL)") (class "Default")
      (node (ref "U$1") (pin "35") (pinfunction "OUT2A_35") (pintype "bidirectional"))
      (node (ref "U$1") (pin "36") (pinfunction "OUT2A_36") (pintype "bidirectional"))
      (node (ref "X1") (pin "5") (pinfunction "KL_5") (pintype "passive"))
    )
    (net (code "143") (name "Net-(X1I-KL)") (class "Default")
      (node (ref "U$1") (pin "2") (pinfunction "OUT1A_2") (pintype "bidirectional"))
      (node (ref "U$1") (pin "3") (pinfunction "OUT1A_3") (pintype "bidirectional"))
      (node (ref "X1") (pin "6") (pinfunction "KL_6") (pintype "passive"))
    )
    (net (code "144") (name "Net-(X1J-KL)") (class "Default")
      (node (ref "R4") (pin "1") (pinfunction "1_1") (pintype "passive"))
      (node (ref "X1") (pin "7") (pinfunction "KL_7") (pintype "passive"))
    )
    (net (code "145") (name "Net-(X1K-KL)") (class "Default")
      (node (ref "U$2") (pin "17") (pinfunction "OUT1B_17") (pintype "bidirectional"))
      (node (ref "U$2") (pin "18") (pinfunction "OUT1B_18") (pintype "bidirectional"))
      (node (ref "X1") (pin "8") (pinfunction "KL_8") (pintype "passive"))
    )
    (net (code "146") (name "Net-(X1L-KL)") (class "Default")
      (node (ref "U$2") (pin "20") (pinfunction "OUT2B_20") (pintype "bidirectional"))
      (node (ref "U$2") (pin "21") (pinfunction "OUT2B_21") (pintype "bidirectional"))
      (node (ref "X1") (pin "9") (pinfunction "KL_9") (pintype "passive"))
    )
    (net (code "147") (name "STEPCLOCK_A") (class "Default")
      (node (ref "SCLKA") (pin "10") (pinfunction "10_10") (pintype "passive"))
      (node (ref "SCLKA") (pin "11") (pinfunction "11_11") (pintype "passive"))
      (node (ref "SCLKA") (pin "12") (pinfunction "12_12") (pintype "passive"))
      (node (ref "SCLKA") (pin "13") (pinfunction "13_13") (pintype "passive"))
      (node (ref "SCLKA") (pin "14") (pinfunction "14_14") (pintype "passive"))
      (node (ref "SCLKA") (pin "15") (pinfunction "15_15") (pintype "passive"))
      (node (ref "SCLKA") (pin "16") (pinfunction "16_16") (pintype "passive"))
      (node (ref "SCLKA") (pin "9") (pinfunction "9_9") (pintype "passive"))
      (node (ref "U$1") (pin "32") (pinfunction "STCK_32") (pintype "bidirectional"))
    )
    (net (code "148") (name "STEPCLOCK_B") (class "Default")
      (node (ref "SCLKB") (pin "10") (pinfunction "10_10") (pintype "passive"))
      (node (ref "SCLKB") (pin "11") (pinfunction "11_11") (pintype "passive"))
      (node (ref "SCLKB") (pin "12") (pinfunction "12_12") (pintype "passive"))
      (node (ref "SCLKB") (pin "13") (pinfunction "13_13") (pintype "passive"))
      (node (ref "SCLKB") (pin "14") (pinfunction "14_14") (pintype "passive"))
      (node (ref "SCLKB") (pin "15") (pinfunction "15_15") (pintype "passive"))
      (node (ref "SCLKB") (pin "16") (pinfunction "16_16") (pintype "passive"))
      (node (ref "SCLKB") (pin "9") (pinfunction "9_9") (pintype "passive"))
      (node (ref "U$2") (pin "32") (pinfunction "STCK_32") (pintype "bidirectional"))
    )
    (net (code "149") (name "V+") (class "Default")
      (node (ref "C10") (pin "+") (pinfunction "+_+") (pintype "passive"))
      (node (ref "C11") (pin "1") (pinfunction "1_1") (pintype "passive"))
      (node (ref "C2") (pin "2") (pinfunction "2_2") (pintype "passive"))
      (node (ref "C4") (pin "2") (pinfunction "2_2") (pintype "passive"))
      (node (ref "C5") (pin "+") (pinfunction "+_+") (pintype "passive"))
      (node (ref "C6") (pin "1") (pinfunction "1_1") (pintype "passive"))
      (node (ref "D1") (pin "1") (pinfunction "A_1") (pintype "passive"))
      (node (ref "D2") (pin "1") (pinfunction "A_1") (pintype "passive"))
      (node (ref "R8") (pin "1") (pinfunction "1_1") (pintype "passive"))
      (node (ref "U$1") (pin "15") (pinfunction "VSB_15") (pintype "bidirectional"))
      (node (ref "U$1") (pin "16") (pinfunction "VSB_16") (pintype "bidirectional"))
      (node (ref "U$1") (pin "22") (pinfunction "VSB2_22") (pintype "bidirectional"))
      (node (ref "U$1") (pin "23") (pinfunction "VSB2_23") (pintype "bidirectional"))
      (node (ref "U$1") (pin "33") (pinfunction "VSA2_33") (pintype "bidirectional"))
      (node (ref "U$1") (pin "34") (pinfunction "VSA2_34") (pintype "bidirectional"))
      (node (ref "U$1") (pin "4") (pinfunction "VSA_4") (pintype "bidirectional"))
      (node (ref "U$1") (pin "5") (pinfunction "VSA_5") (pintype "bidirectional"))
      (node (ref "U$2") (pin "15") (pinfunction "VSB_15") (pintype "bidirectional"))
      (node (ref "U$2") (pin "16") (pinfunction "VSB_16") (pintype "bidirectional"))
      (node (ref "U$2") (pin "22") (pinfunction "VSB2_22") (pintype "bidirectional"))
      (node (ref "U$2") (pin "23") (pinfunction "VSB2_23") (pintype "bidirectional"))
      (node (ref "U$2") (pin "33") (pinfunction "VSA2_33") (pintype "bidirectional"))
      (node (ref "U$2") (pin "34") (pinfunction "VSA2_34") (pintype "bidirectional"))
      (node (ref "U$2") (pin "4") (pinfunction "VSA_4") (pintype "bidirectional"))
      (node (ref "U$2") (pin "5") (pinfunction "VSA_5") (pintype "bidirectional"))
      (node (ref "X1") (pin "1") (pinfunction "KL_1") (pintype "passive"))
    )
    (net (code "150") (name "unconnected-(U$1-OSCIN-Pad10)") (class "Default")
      (node (ref "U$1") (pin "10") (pinfunction "OSCIN_10") (pintype "bidirectional"))
    )
    (net (code "151") (name "unconnected-(U$1-OSCOUT-Pad11)") (class "Default")
      (node (ref "U$1") (pin "11") (pinfunction "OSCOUT_11") (pintype "bidirectional"))
    )
    (net (code "152") (name "unconnected-(U$2-OSCIN-Pad10)") (class "Default")
      (node (ref "U$2") (pin "10") (pinfunction "OSCIN_10") (pintype "bidirectional"))
    )
    (net (code "153") (name "unconnected-(U$2-OSCOUT-Pad11)") (class "Default")
      (node (ref "U$2") (pin "11") (pinfunction "OSCOUT_11") (pintype "bidirectional"))
    )
  )
)
